# CH32V317W-R0-1v0.net
KiCad netlist of a schematic drawn in Altium Designer
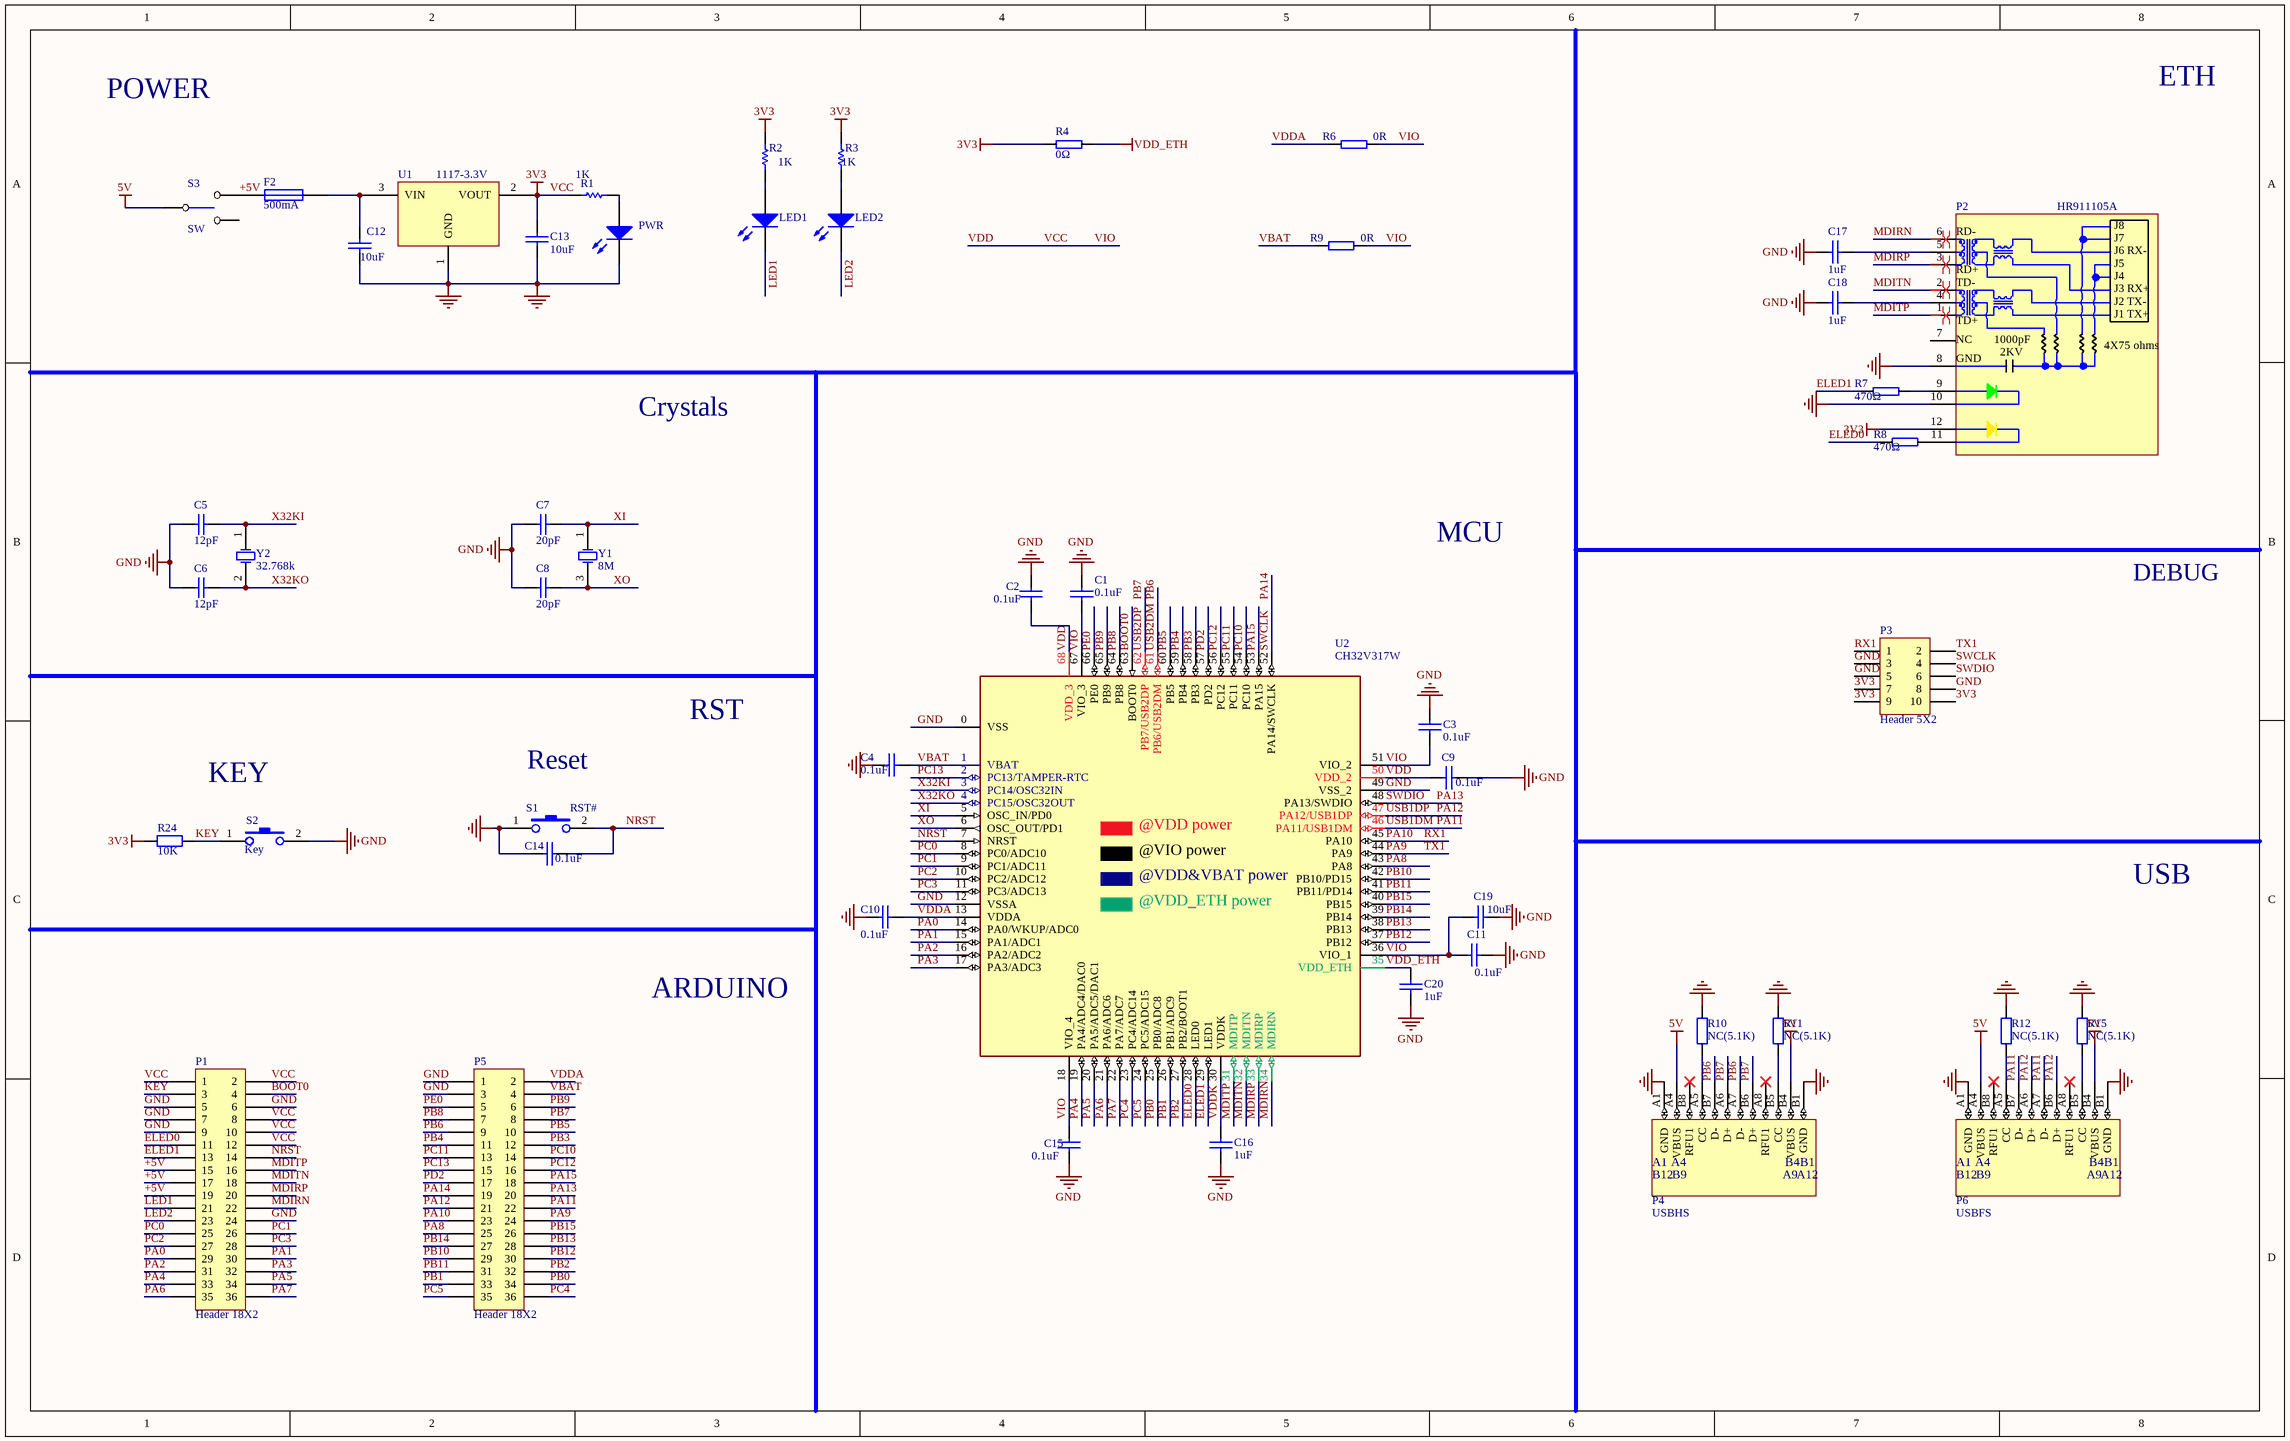
[diagram p0: CH32V317W-R0-1v0.SchDoc]

(export (version "E")
  (design (tool "Eeschema 10.0.6"))
  (components
    (comp (ref "C1")
      (value "0.1uF")
      (footprint "0603_C")
      (description "Capacitor")
      (libsource (lib "*") (part "CAP"))
    )
    (comp (ref "C2")
      (value "0.1uF")
      (footprint "0603_C")
      (description "Capacitor")
      (libsource (lib "*") (part "CAP"))
    )
    (comp (ref "C3")
      (value "0.1uF")
      (footprint "0603_C")
      (description "Capacitor")
      (libsource (lib "*") (part "CAP"))
    )
    (comp (ref "C4")
      (value "0.1uF")
      (footprint "0603_C")
      (description "Capacitor")
      (libsource (lib "*") (part "CAP"))
    )
    (comp (ref "C5")
      (value "12pF")
      (footprint "0603_C")
      (description "Capacitor")
      (libsource (lib "Miscellaneous Devices") (part "Cap"))
    )
    (comp (ref "C6")
      (value "12pF")
      (footprint "0603_C")
      (description "Capacitor")
      (libsource (lib "Miscellaneous Devices") (part "Cap"))
    )
    (comp (ref "C7")
      (value "20pF")
      (footprint "0603_C")
      (description "Capacitor")
      (libsource (lib "Miscellaneous Devices") (part "Cap"))
    )
    (comp (ref "C8")
      (value "20pF")
      (footprint "0603_C")
      (description "Capacitor")
      (libsource (lib "Miscellaneous Devices") (part "Cap"))
    )
    (comp (ref "C9")
      (value "0.1uF")
      (footprint "0603_C")
      (description "Capacitor")
      (libsource (lib "*") (part "CAP"))
    )
    (comp (ref "C10")
      (value "0.1uF")
      (footprint "0603_C")
      (description "Capacitor")
      (libsource (lib "*") (part "CAP"))
    )
    (comp (ref "C11")
      (value "0.1uF")
      (footprint "0603_C")
      (description "Capacitor")
      (libsource (lib "*") (part "CAP"))
    )
    (comp (ref "C12")
      (value "10uF")
      (footprint "0603_C")
      (description "Capacitor")
      (libsource (lib "*") (part "CAP"))
    )
    (comp (ref "C13")
      (value "10uF")
      (footprint "0603_C")
      (description "Capacitor")
      (libsource (lib "*") (part "CAP"))
    )
    (comp (ref "C14")
      (value "0.1uF")
      (footprint "0603_C")
      (description "Capacitor")
      (libsource (lib "") (part "CAP_1"))
    )
    (comp (ref "C15")
      (value "0.1uF")
      (footprint "0603_C")
      (description "Capacitor")
      (libsource (lib "*") (part "CAP"))
    )
    (comp (ref "C16")
      (value "1uF")
      (footprint "0603_C")
      (description "Capacitor")
      (libsource (lib "wch_sch_others") (part "CAP"))
    )
    (comp (ref "C17")
      (value "1uF")
      (footprint "0603_C")
      (description "Capacitor")
      (libsource (lib "wch_sch_others") (part "CAP"))
    )
    (comp (ref "C18")
      (value "1uF")
      (footprint "0603_C")
      (description "Capacitor")
      (libsource (lib "wch_sch_others") (part "CAP"))
    )
    (comp (ref "C19")
      (value "10uF")
      (footprint "0603_C")
      (description "Capacitor")
      (libsource (lib "*") (part "CAP"))
    )
    (comp (ref "C20")
      (value "1uF")
      (footprint "0603_C")
      (description "Capacitor")
      (libsource (lib "*") (part "CAP"))
    )
    (comp (ref "F2")
      (value "500mA")
      (footprint "0603")
      (description "Fuse")
      (libsource (lib "*") (part "FUSE1"))
    )
    (comp (ref "LED1")
      (value "LED1   blue")
      (footprint "0603+")
      (description "Typical INFRARED GaAs LED")
      (fields (field (name "PUBLISHER") "Altium Limited"))
      (libsource (lib "Miscellaneous Devices") (part "LED0"))
    )
    (comp (ref "LED2")
      (value "LED2  blue")
      (footprint "0603+")
      (description "Typical INFRARED GaAs LED")
      (fields (field (name "PUBLISHER") "Altium Limited"))
      (libsource (lib "Miscellaneous Devices") (part "LED0"))
    )
    (comp (ref "P1")
      (value "Header 18X2")
      (footprint "IDC36-2.54mm")
      (description "Header, 18-Pin, Dual row")
      (fields (field (name "PUBLISHER") "Altium Limited"))
      (libsource (lib "Miscellaneous Connectors") (part "Header 18X2"))
    )
    (comp (ref "P2") (value "HR911105A") (footprint "HR911105A") (libsource (lib "*") (part "HR911105A")))
    (comp (ref "P3")
      (value "Header 5X2")
      (footprint "IDC10-2.54mm")
      (description "Header, 5-Pin, Dual row")
      (fields (field (name "PUBLISHER") "Altium Limited"))
      (libsource (lib "Miscellaneous Connectors") (part "Header 5X2"))
    )
    (comp (ref "P4")
      (value "USBHS")
      (footprint "TYPE-C-Receptacle-2.0")
      (libsource (lib "*") (part "TYPE-C1"))
    )
    (comp (ref "P5")
      (value "Header 18X2")
      (footprint "IDC36-2.54mm")
      (description "Header, 18-Pin, Dual row")
      (fields (field (name "PUBLISHER") "Altium Limited"))
      (libsource (lib "Miscellaneous Connectors") (part "Header 18X2"))
    )
    (comp (ref "P6")
      (value "USBFS")
      (footprint "TYPE-C-Receptacle-2.0")
      (libsource (lib "*") (part "TYPE-C1"))
    )
    (comp (ref "PWR")
      (value "POWER  red")
      (footprint "0603+")
      (description "Typical INFRARED GaAs LED")
      (fields (field (name "PUBLISHER") "Altium Limited"))
      (libsource (lib "Miscellaneous Devices") (part "LED0"))
    )
    (comp (ref "R1")
      (value "1K")
      (footprint "0603")
      (description "Semiconductor Resistor")
      (libsource (lib "Miscellaneous Devices") (part "Res Semi"))
    )
    (comp (ref "R2")
      (value "1K")
      (footprint "0603")
      (description "Semiconductor Resistor")
      (libsource (lib "Miscellaneous Devices") (part "Res Semi"))
    )
    (comp (ref "R3")
      (value "1K")
      (footprint "0603")
      (description "Semiconductor Resistor")
      (libsource (lib "Miscellaneous Devices") (part "Res Semi"))
    )
    (comp (ref "R4") (value "0Ω") (footprint "0603") (libsource (lib "") (part "RES_1")))
    (comp (ref "R6") (value "0R") (footprint "0603") (libsource (lib "*") (part "R")))
    (comp (ref "R7") (value "470Ω") (footprint "0603") (libsource (lib "wch_sch_others") (part "RES")))
    (comp (ref "R8") (value "470Ω") (footprint "0603") (libsource (lib "wch_sch_others") (part "RES")))
    (comp (ref "R9") (value "0R") (footprint "0603") (libsource (lib "*") (part "R")))
    (comp (ref "R10")
      (value "NC(5.1K)")
      (footprint "0603")
      (description "Resistor")
      (libsource (lib "") (part "Res2_1"))
    )
    (comp (ref "R11")
      (value "NC(5.1K)")
      (footprint "0603")
      (description "Resistor")
      (libsource (lib "") (part "Res2_1"))
    )
    (comp (ref "R12")
      (value "NC(5.1K)")
      (footprint "0603")
      (description "Resistor")
      (libsource (lib "") (part "Res2_1"))
    )
    (comp (ref "R15")
      (value "NC(5.1K)")
      (footprint "0603")
      (description "Resistor")
      (libsource (lib "") (part "Res2_1"))
    )
    (comp (ref "R24")
      (value "10K")
      (footprint "0603")
      (description "Resistor")
      (libsource (lib "Miscellaneous Devices") (part "Res2"))
    )
    (comp (ref "S1")
      (value "RST#")
      (footprint "SMD_6.1x3.65x2.5mm-KEY")
      (libsource (lib "wch_sch_others") (part "KEY1"))
    )
    (comp (ref "S2")
      (value "Key")
      (footprint "SMD_6.1x3.65x2.5mm-KEY")
      (libsource (lib "wch_sch_others") (part "KEY1"))
    )
    (comp (ref "S3") (value "SW") (footprint "SW1") (libsource (lib "MYSCH") (part "SW")))
    (comp (ref "U1")
      (value "1117-3.3V")
      (footprint "SOT-223")
      (libsource (lib "wch_sch_others") (part "1117-3.3V"))
    )
    (comp (ref "U2")
      (value "CH32V317W")
      (footprint "QFN68_8X8")
      (description "RISC-V FPU HD-MCU, 144MHz, USB_480M, USB OTG, 100M Ethernet & Phy, 2*CAN")
      (libsource (lib "CHXXX") (part "CH32V317W"))
    )
    (comp (ref "Y1")
      (value "8M")
      (footprint "XT3225")
      (description "Crystal Oscillator")
      (fields (field (name "PUBLISHER") "Altium Limited"))
      (libsource (lib "") (part "XTAL_1"))
    )
    (comp (ref "Y2")
      (value "32.768k")
      (footprint "FC-135")
      (description "Crystal Oscillator")
      (fields (field (name "PUBLISHER") "Altium Limited"))
      (libsource (lib "Miscellaneous Devices") (part "XTAL"))
    )
  )
  (nets
    (net (code "1") (name "/+5V") (class "Default")
      (node (ref "F2") (pin "1") (pinfunction "1_1") (pintype "passive"))
      (node (ref "P1") (pin "15") (pinfunction "15_15") (pintype "passive"))
      (node (ref "P1") (pin "17") (pinfunction "17_17") (pintype "passive"))
      (node (ref "P1") (pin "19") (pinfunction "19_19") (pintype "passive"))
      (node (ref "S3") (pin "3") (pinfunction "3_3") (pintype "passive"))
    )
    (net (code "2") (name "/BOOT0") (class "Default")
      (node (ref "P1") (pin "4") (pinfunction "4_4") (pintype "passive"))
      (node (ref "U2") (pin "63") (pinfunction "BOOT0_63") (pintype "input"))
    )
    (net (code "3") (name "/ELED0") (class "Default")
      (node (ref "P1") (pin "11") (pinfunction "11_11") (pintype "passive"))
      (node (ref "R8") (pin "1") (pintype "passive"))
      (node (ref "U2") (pin "28") (pinfunction "LED0_28") (pintype "bidirectional"))
    )
    (net (code "4") (name "/ELED1") (class "Default")
      (node (ref "P1") (pin "13") (pinfunction "13_13") (pintype "passive"))
      (node (ref "R7") (pin "1") (pintype "passive"))
      (node (ref "U2") (pin "29") (pinfunction "LED1_29") (pintype "bidirectional"))
    )
    (net (code "5") (name "/KEY") (class "Default")
      (node (ref "P1") (pin "3") (pinfunction "3_3") (pintype "passive"))
      (node (ref "R24") (pin "1") (pinfunction "1_1") (pintype "passive"))
      (node (ref "S2") (pin "1") (pinfunction "1_1") (pintype "passive"))
    )
    (net (code "6") (name "/LED1") (class "Default")
      (node (ref "LED1") (pin "2") (pinfunction "K_2") (pintype "passive"))
      (node (ref "P1") (pin "21") (pinfunction "21_21") (pintype "passive"))
    )
    (net (code "7") (name "/LED2") (class "Default")
      (node (ref "LED2") (pin "2") (pinfunction "K_2") (pintype "passive"))
      (node (ref "P1") (pin "23") (pinfunction "23_23") (pintype "passive"))
    )
    (net (code "8") (name "/MDIRN") (class "Default")
      (node (ref "P1") (pin "22") (pinfunction "22_22") (pintype "passive"))
      (node (ref "P2") (pin "6") (pintype "passive"))
      (node (ref "U2") (pin "34") (pinfunction "MDIRN_34") (pintype "bidirectional"))
    )
    (net (code "9") (name "/MDIRP") (class "Default")
      (node (ref "P1") (pin "20") (pinfunction "20_20") (pintype "passive"))
      (node (ref "P2") (pin "3") (pintype "passive"))
      (node (ref "U2") (pin "33") (pinfunction "MDIRP_33") (pintype "bidirectional"))
    )
    (net (code "10") (name "/MDITN") (class "Default")
      (node (ref "P1") (pin "18") (pinfunction "18_18") (pintype "passive"))
      (node (ref "P2") (pin "2") (pintype "passive"))
      (node (ref "U2") (pin "32") (pinfunction "MDITN_32") (pintype "bidirectional"))
    )
    (net (code "11") (name "/MDITP") (class "Default")
      (node (ref "P1") (pin "16") (pinfunction "16_16") (pintype "passive"))
      (node (ref "P2") (pin "1") (pintype "passive"))
      (node (ref "U2") (pin "31") (pinfunction "MDITP_31") (pintype "bidirectional"))
    )
    (net (code "12") (name "/NRST") (class "Default")
      (node (ref "C14") (pin "2") (pinfunction "2_2") (pintype "passive"))
      (node (ref "P1") (pin "14") (pinfunction "14_14") (pintype "passive"))
      (node (ref "S1") (pin "2") (pinfunction "2_2") (pintype "passive"))
      (node (ref "U2") (pin "7") (pinfunction "NRST_7") (pintype "input"))
    )
    (net (code "13") (name "/PA0") (class "Default")
      (node (ref "P1") (pin "29") (pinfunction "29_29") (pintype "passive"))
      (node (ref "U2") (pin "14") (pinfunction "PA0/WKUP/ADC0_14") (pintype "bidirectional"))
    )
    (net (code "14") (name "/PA1") (class "Default")
      (node (ref "P1") (pin "30") (pinfunction "30_30") (pintype "passive"))
      (node (ref "U2") (pin "15") (pinfunction "PA1/ADC1_15") (pintype "bidirectional"))
    )
    (net (code "15") (name "/PA2") (class "Default")
      (node (ref "P1") (pin "31") (pinfunction "31_31") (pintype "passive"))
      (node (ref "U2") (pin "16") (pinfunction "PA2/ADC2_16") (pintype "bidirectional"))
    )
    (net (code "16") (name "/PA3") (class "Default")
      (node (ref "P1") (pin "32") (pinfunction "32_32") (pintype "passive"))
      (node (ref "U2") (pin "17") (pinfunction "PA3/ADC3_17") (pintype "bidirectional"))
    )
    (net (code "17") (name "/PA4") (class "Default")
      (node (ref "P1") (pin "33") (pinfunction "33_33") (pintype "passive"))
      (node (ref "U2") (pin "19") (pinfunction "PA4/ADC4/DAC0_19") (pintype "bidirectional"))
    )
    (net (code "18") (name "/PA5") (class "Default")
      (node (ref "P1") (pin "34") (pinfunction "34_34") (pintype "passive"))
      (node (ref "U2") (pin "20") (pinfunction "PA5/ADC5/DAC1_20") (pintype "bidirectional"))
    )
    (net (code "19") (name "/PA6") (class "Default")
      (node (ref "P1") (pin "35") (pinfunction "35_35") (pintype "passive"))
      (node (ref "U2") (pin "21") (pinfunction "PA6/ADC6_21") (pintype "bidirectional"))
    )
    (net (code "20") (name "/PA7") (class "Default")
      (node (ref "P1") (pin "36") (pinfunction "36_36") (pintype "passive"))
      (node (ref "U2") (pin "22") (pinfunction "PA7/ADC7_22") (pintype "bidirectional"))
    )
    (net (code "21") (name "/PA8") (class "Default")
      (node (ref "P5") (pin "25") (pinfunction "25_25") (pintype "passive"))
      (node (ref "U2") (pin "43") (pinfunction "PA8_43") (pintype "bidirectional"))
    )
    (net (code "22") (name "/PA9") (class "Default")
      (node (ref "P3") (pin "2") (pinfunction "2_2") (pintype "passive"))
      (node (ref "P5") (pin "24") (pinfunction "24_24") (pintype "passive"))
      (node (ref "U2") (pin "44") (pinfunction "PA9_44") (pintype "bidirectional"))
    )
    (net (code "23") (name "/PA10") (class "Default")
      (node (ref "P3") (pin "1") (pinfunction "1_1") (pintype "passive"))
      (node (ref "P5") (pin "23") (pinfunction "23_23") (pintype "passive"))
      (node (ref "U2") (pin "45") (pinfunction "PA10_45") (pintype "bidirectional"))
    )
    (net (code "24") (name "/PA11") (class "Default")
      (node (ref "P5") (pin "22") (pinfunction "22_22") (pintype "passive"))
      (node (ref "P6") (pin "A7") (pinfunction "D-_A7") (pintype "bidirectional"))
      (node (ref "P6") (pin "B7") (pinfunction "D-_B7") (pintype "bidirectional"))
      (node (ref "U2") (pin "46") (pinfunction "PA11/USB1DM_46") (pintype "bidirectional"))
    )
    (net (code "25") (name "/PA12") (class "Default")
      (node (ref "P5") (pin "21") (pinfunction "21_21") (pintype "passive"))
      (node (ref "P6") (pin "A6") (pinfunction "D+_A6") (pintype "bidirectional"))
      (node (ref "P6") (pin "B6") (pinfunction "D+_B6") (pintype "bidirectional"))
      (node (ref "U2") (pin "47") (pinfunction "PA12/USB1DP_47") (pintype "bidirectional"))
    )
    (net (code "26") (name "/PA13") (class "Default")
      (node (ref "P3") (pin "6") (pinfunction "6_6") (pintype "passive"))
      (node (ref "P5") (pin "20") (pinfunction "20_20") (pintype "passive"))
      (node (ref "U2") (pin "48") (pinfunction "PA13/SWDIO_48") (pintype "bidirectional"))
    )
    (net (code "27") (name "/PA14") (class "Default")
      (node (ref "P3") (pin "4") (pinfunction "4_4") (pintype "passive"))
      (node (ref "P5") (pin "19") (pinfunction "19_19") (pintype "passive"))
      (node (ref "U2") (pin "52") (pinfunction "PA14/SWCLK_52") (pintype "bidirectional"))
    )
    (net (code "28") (name "/PA15") (class "Default")
      (node (ref "P5") (pin "18") (pinfunction "18_18") (pintype "passive"))
      (node (ref "U2") (pin "53") (pinfunction "PA15_53") (pintype "bidirectional"))
    )
    (net (code "29") (name "/PB0") (class "Default")
      (node (ref "P5") (pin "34") (pinfunction "34_34") (pintype "passive"))
      (node (ref "U2") (pin "25") (pinfunction "PB0/ADC8_25") (pintype "bidirectional"))
    )
    (net (code "30") (name "/PB1") (class "Default")
      (node (ref "P5") (pin "33") (pinfunction "33_33") (pintype "passive"))
      (node (ref "U2") (pin "26") (pinfunction "PB1/ADC9_26") (pintype "bidirectional"))
    )
    (net (code "31") (name "/PB2") (class "Default")
      (node (ref "P5") (pin "32") (pinfunction "32_32") (pintype "passive"))
      (node (ref "U2") (pin "27") (pinfunction "PB2/BOOT1_27") (pintype "bidirectional"))
    )
    (net (code "32") (name "/PB3") (class "Default")
      (node (ref "P5") (pin "12") (pinfunction "12_12") (pintype "passive"))
      (node (ref "U2") (pin "58") (pinfunction "PB3_58") (pintype "bidirectional"))
    )
    (net (code "33") (name "/PB4") (class "Default")
      (node (ref "P5") (pin "11") (pinfunction "11_11") (pintype "passive"))
      (node (ref "U2") (pin "59") (pinfunction "PB4_59") (pintype "bidirectional"))
    )
    (net (code "34") (name "/PB5") (class "Default")
      (node (ref "P5") (pin "10") (pinfunction "10_10") (pintype "passive"))
      (node (ref "U2") (pin "60") (pinfunction "PB5_60") (pintype "bidirectional"))
    )
    (net (code "35") (name "/PB6") (class "Default")
      (node (ref "P4") (pin "A7") (pinfunction "D-_A7") (pintype "bidirectional"))
      (node (ref "P4") (pin "B7") (pinfunction "D-_B7") (pintype "bidirectional"))
      (node (ref "P5") (pin "9") (pinfunction "9_9") (pintype "passive"))
      (node (ref "U2") (pin "61") (pinfunction "PB6/USB2DM_61") (pintype "bidirectional"))
    )
    (net (code "36") (name "/PB7") (class "Default")
      (node (ref "P4") (pin "A6") (pinfunction "D+_A6") (pintype "bidirectional"))
      (node (ref "P4") (pin "B6") (pinfunction "D+_B6") (pintype "bidirectional"))
      (node (ref "P5") (pin "8") (pinfunction "8_8") (pintype "passive"))
      (node (ref "U2") (pin "62") (pinfunction "PB7/USB2DP_62") (pintype "bidirectional"))
    )
    (net (code "37") (name "/PB8") (class "Default")
      (node (ref "P5") (pin "7") (pinfunction "7_7") (pintype "passive"))
      (node (ref "U2") (pin "64") (pinfunction "PB8_64") (pintype "bidirectional"))
    )
    (net (code "38") (name "/PB9") (class "Default")
      (node (ref "P5") (pin "6") (pinfunction "6_6") (pintype "passive"))
      (node (ref "U2") (pin "65") (pinfunction "PB9_65") (pintype "bidirectional"))
    )
    (net (code "39") (name "/PB10") (class "Default")
      (node (ref "P5") (pin "29") (pinfunction "29_29") (pintype "passive"))
      (node (ref "U2") (pin "42") (pinfunction "PB10/PD15_42") (pintype "bidirectional"))
    )
    (net (code "40") (name "/PB11") (class "Default")
      (node (ref "P5") (pin "31") (pinfunction "31_31") (pintype "passive"))
      (node (ref "U2") (pin "41") (pinfunction "PB11/PD14_41") (pintype "bidirectional"))
    )
    (net (code "41") (name "/PB12") (class "Default")
      (node (ref "P5") (pin "30") (pinfunction "30_30") (pintype "passive"))
      (node (ref "U2") (pin "37") (pinfunction "PB12_37") (pintype "bidirectional"))
    )
    (net (code "42") (name "/PB13") (class "Default")
      (node (ref "P5") (pin "28") (pinfunction "28_28") (pintype "passive"))
      (node (ref "U2") (pin "38") (pinfunction "PB13_38") (pintype "bidirectional"))
    )
    (net (code "43") (name "/PB14") (class "Default")
      (node (ref "P5") (pin "27") (pinfunction "27_27") (pintype "passive"))
      (node (ref "U2") (pin "39") (pinfunction "PB14_39") (pintype "bidirectional"))
    )
    (net (code "44") (name "/PB15") (class "Default")
      (node (ref "P5") (pin "26") (pinfunction "26_26") (pintype "passive"))
      (node (ref "U2") (pin "40") (pinfunction "PB15_40") (pintype "bidirectional"))
    )
    (net (code "45") (name "/PC0") (class "Default")
      (node (ref "P1") (pin "25") (pinfunction "25_25") (pintype "passive"))
      (node (ref "U2") (pin "8") (pinfunction "PC0/ADC10_8") (pintype "bidirectional"))
    )
    (net (code "46") (name "/PC1") (class "Default")
      (node (ref "P1") (pin "26") (pinfunction "26_26") (pintype "passive"))
      (node (ref "U2") (pin "9") (pinfunction "PC1/ADC11_9") (pintype "bidirectional"))
    )
    (net (code "47") (name "/PC2") (class "Default")
      (node (ref "P1") (pin "27") (pinfunction "27_27") (pintype "passive"))
      (node (ref "U2") (pin "10") (pinfunction "PC2/ADC12_10") (pintype "bidirectional"))
    )
    (net (code "48") (name "/PC3") (class "Default")
      (node (ref "P1") (pin "28") (pinfunction "28_28") (pintype "passive"))
      (node (ref "U2") (pin "11") (pinfunction "PC3/ADC13_11") (pintype "bidirectional"))
    )
    (net (code "49") (name "/PC4") (class "Default")
      (node (ref "P5") (pin "36") (pinfunction "36_36") (pintype "passive"))
      (node (ref "U2") (pin "23") (pinfunction "PC4/ADC14_23") (pintype "bidirectional"))
    )
    (net (code "50") (name "/PC5") (class "Default")
      (node (ref "P5") (pin "35") (pinfunction "35_35") (pintype "passive"))
      (node (ref "U2") (pin "24") (pinfunction "PC5/ADC15_24") (pintype "bidirectional"))
    )
    (net (code "51") (name "/PC10") (class "Default")
      (node (ref "P5") (pin "14") (pinfunction "14_14") (pintype "passive"))
      (node (ref "U2") (pin "54") (pinfunction "PC10_54") (pintype "bidirectional"))
    )
    (net (code "52") (name "/PC11") (class "Default")
      (node (ref "P5") (pin "13") (pinfunction "13_13") (pintype "passive"))
      (node (ref "U2") (pin "55") (pinfunction "PC11_55") (pintype "bidirectional"))
    )
    (net (code "53") (name "/PC12") (class "Default")
      (node (ref "P5") (pin "16") (pinfunction "16_16") (pintype "passive"))
      (node (ref "U2") (pin "56") (pinfunction "PC12_56") (pintype "bidirectional"))
    )
    (net (code "54") (name "/PC13") (class "Default")
      (node (ref "P5") (pin "15") (pinfunction "15_15") (pintype "passive"))
      (node (ref "U2") (pin "2") (pinfunction "PC13/TAMPER-RTC_2") (pintype "bidirectional"))
    )
    (net (code "55") (name "/PD2") (class "Default")
      (node (ref "P5") (pin "17") (pinfunction "17_17") (pintype "passive"))
      (node (ref "U2") (pin "57") (pinfunction "PD2_57") (pintype "bidirectional"))
    )
    (net (code "56") (name "/PE0") (class "Default")
      (node (ref "P5") (pin "5") (pinfunction "5_5") (pintype "passive"))
      (node (ref "U2") (pin "66") (pinfunction "PE0_66") (pintype "bidirectional"))
    )
    (net (code "57") (name "/VBAT") (class "Default")
      (node (ref "C4") (pin "2") (pinfunction "2_2") (pintype "passive"))
      (node (ref "P5") (pin "4") (pinfunction "4_4") (pintype "passive"))
      (node (ref "R9") (pin "2") (pinfunction "2_2") (pintype "passive"))
      (node (ref "U2") (pin "1") (pinfunction "VBAT_1") (pintype "power_in"))
    )
    (net (code "58") (name "/VDDA") (class "Default")
      (node (ref "C10") (pin "1") (pinfunction "1_1") (pintype "passive"))
      (node (ref "P5") (pin "2") (pinfunction "2_2") (pintype "passive"))
      (node (ref "R6") (pin "2") (pinfunction "2_2") (pintype "passive"))
      (node (ref "U2") (pin "13") (pinfunction "VDDA_13") (pintype "power_in"))
    )
    (net (code "59") (name "/VDDK") (class "Default")
      (node (ref "C16") (pin "2") (pinfunction "2_2") (pintype "passive"))
      (node (ref "U2") (pin "30") (pinfunction "VDDK_30") (pintype "power_in"))
    )
    (net (code "60") (name "/X32KI") (class "Default")
      (node (ref "C5") (pin "1") (pinfunction "1_1") (pintype "passive"))
      (node (ref "U2") (pin "3") (pinfunction "PC14/OSC32IN_3") (pintype "bidirectional"))
      (node (ref "Y2") (pin "1") (pinfunction "OSC1_1") (pintype "passive"))
    )
    (net (code "61") (name "/X32KO") (class "Default")
      (node (ref "C6") (pin "1") (pinfunction "1_1") (pintype "passive"))
      (node (ref "U2") (pin "4") (pinfunction "PC15/OSC32OUT_4") (pintype "bidirectional"))
      (node (ref "Y2") (pin "2") (pinfunction "OSC2_2") (pintype "passive"))
    )
    (net (code "62") (name "/XI") (class "Default")
      (node (ref "C7") (pin "2") (pinfunction "2_2") (pintype "passive"))
      (node (ref "U2") (pin "5") (pinfunction "OSC_IN/PD0_5") (pintype "input"))
      (node (ref "Y1") (pin "1") (pinfunction "OSC1_1") (pintype "passive"))
    )
    (net (code "63") (name "/XO") (class "Default")
      (node (ref "C8") (pin "2") (pinfunction "2_2") (pintype "passive"))
      (node (ref "U2") (pin "6") (pinfunction "OSC_OUT/PD1_6") (pintype "output"))
      (node (ref "Y1") (pin "3") (pinfunction "OSC2_3") (pintype "passive"))
    )
    (net (code "64") (name "3V3") (class "Default")
      (node (ref "C1") (pin "2") (pinfunction "2_2") (pintype "passive"))
      (node (ref "C11") (pin "2") (pinfunction "2_2") (pintype "passive"))
      (node (ref "C13") (pin "1") (pinfunction "1_1") (pintype "passive"))
      (node (ref "C15") (pin "2") (pinfunction "2_2") (pintype "passive"))
      (node (ref "C19") (pin "2") (pinfunction "2_2") (pintype "passive"))
      (node (ref "C2") (pin "2") (pinfunction "2_2") (pintype "passive"))
      (node (ref "C3") (pin "2") (pinfunction "2_2") (pintype "passive"))
      (node (ref "C9") (pin "2") (pinfunction "2_2") (pintype "passive"))
      (node (ref "P1") (pin "1") (pinfunction "1_1") (pintype "passive"))
      (node (ref "P1") (pin "10") (pinfunction "10_10") (pintype "passive"))
      (node (ref "P1") (pin "12") (pinfunction "12_12") (pintype "passive"))
      (node (ref "P1") (pin "2") (pinfunction "2_2") (pintype "passive"))
      (node (ref "P1") (pin "8") (pinfunction "8_8") (pintype "passive"))
      (node (ref "P2") (pin "12") (pintype "passive"))
      (node (ref "P3") (pin "10") (pinfunction "10_10") (pintype "passive"))
      (node (ref "P3") (pin "7") (pinfunction "7_7") (pintype "passive"))
      (node (ref "P3") (pin "9") (pinfunction "9_9") (pintype "passive"))
      (node (ref "R1") (pin "2") (pinfunction "2_2") (pintype "passive"))
      (node (ref "R2") (pin "1") (pinfunction "1_1") (pintype "passive"))
      (node (ref "R24") (pin "2") (pinfunction "2_2") (pintype "passive"))
      (node (ref "R3") (pin "1") (pinfunction "1_1") (pintype "passive"))
      (node (ref "R4") (pin "2") (pintype "passive"))
      (node (ref "R6") (pin "1") (pinfunction "1_1") (pintype "passive"))
      (node (ref "R9") (pin "1") (pinfunction "1_1") (pintype "passive"))
      (node (ref "U1") (pin "2") (pinfunction "VOUT_2") (pintype "passive"))
      (node (ref "U2") (pin "18") (pinfunction "VIO_4_18") (pintype "power_in"))
      (node (ref "U2") (pin "36") (pinfunction "VIO_1_36") (pintype "power_in"))
      (node (ref "U2") (pin "50") (pinfunction "VDD_2_50") (pintype "power_in"))
      (node (ref "U2") (pin "51") (pinfunction "VIO_2_51") (pintype "power_in"))
      (node (ref "U2") (pin "67") (pinfunction "VIO_3_67") (pintype "power_in"))
      (node (ref "U2") (pin "68") (pinfunction "VDD_3_68") (pintype "power_in"))
    )
    (net (code "65") (name "5V") (class "Default")
      (node (ref "P4") (pin "A4") (pinfunction "VBUS_A4") (pintype "bidirectional"))
      (node (ref "P4") (pin "B4") (pinfunction "VBUS_B4") (pintype "bidirectional"))
      (node (ref "P6") (pin "A4") (pinfunction "VBUS_A4") (pintype "bidirectional"))
      (node (ref "P6") (pin "B4") (pinfunction "VBUS_B4") (pintype "bidirectional"))
      (node (ref "S3") (pin "1") (pinfunction "1_1") (pintype "passive"))
    )
    (net (code "66") (name "GND") (class "Default")
      (node (ref "C1") (pin "1") (pinfunction "1_1") (pintype "passive"))
      (node (ref "C10") (pin "2") (pinfunction "2_2") (pintype "passive"))
      (node (ref "C11") (pin "1") (pinfunction "1_1") (pintype "passive"))
      (node (ref "C12") (pin "2") (pinfunction "2_2") (pintype "passive"))
      (node (ref "C13") (pin "2") (pinfunction "2_2") (pintype "passive"))
      (node (ref "C14") (pin "1") (pinfunction "1_1") (pintype "passive"))
      (node (ref "C15") (pin "1") (pinfunction "1_1") (pintype "passive"))
      (node (ref "C16") (pin "1") (pinfunction "1_1") (pintype "passive"))
      (node (ref "C17") (pin "1") (pinfunction "1_1") (pintype "passive"))
      (node (ref "C18") (pin "1") (pinfunction "1_1") (pintype "passive"))
      (node (ref "C19") (pin "1") (pinfunction "1_1") (pintype "passive"))
      (node (ref "C2") (pin "1") (pinfunction "1_1") (pintype "passive"))
      (node (ref "C20") (pin "1") (pinfunction "1_1") (pintype "passive"))
      (node (ref "C3") (pin "1") (pinfunction "1_1") (pintype "passive"))
      (node (ref "C4") (pin "1") (pinfunction "1_1") (pintype "passive"))
      (node (ref "C5") (pin "2") (pinfunction "2_2") (pintype "passive"))
      (node (ref "C6") (pin "2") (pinfunction "2_2") (pintype "passive"))
      (node (ref "C7") (pin "1") (pinfunction "1_1") (pintype "passive"))
      (node (ref "C8") (pin "1") (pinfunction "1_1") (pintype "passive"))
      (node (ref "C9") (pin "1") (pinfunction "1_1") (pintype "passive"))
      (node (ref "P1") (pin "24") (pinfunction "24_24") (pintype "passive"))
      (node (ref "P1") (pin "5") (pinfunction "5_5") (pintype "passive"))
      (node (ref "P1") (pin "6") (pinfunction "6_6") (pintype "passive"))
      (node (ref "P1") (pin "7") (pinfunction "7_7") (pintype "passive"))
      (node (ref "P1") (pin "9") (pinfunction "9_9") (pintype "passive"))
      (node (ref "P2") (pin "10") (pintype "passive"))
      (node (ref "P2") (pin "8") (pintype "passive"))
      (node (ref "P3") (pin "3") (pinfunction "3_3") (pintype "passive"))
      (node (ref "P3") (pin "5") (pinfunction "5_5") (pintype "passive"))
      (node (ref "P3") (pin "8") (pinfunction "8_8") (pintype "passive"))
      (node (ref "P4") (pin "A1") (pinfunction "GND_A1") (pintype "bidirectional"))
      (node (ref "P4") (pin "B1") (pinfunction "GND_B1") (pintype "bidirectional"))
      (node (ref "P5") (pin "1") (pinfunction "1_1") (pintype "passive"))
      (node (ref "P5") (pin "3") (pinfunction "3_3") (pintype "passive"))
      (node (ref "P6") (pin "A1") (pinfunction "GND_A1") (pintype "bidirectional"))
      (node (ref "P6") (pin "B1") (pinfunction "GND_B1") (pintype "bidirectional"))
      (node (ref "PWR") (pin "2") (pinfunction "K_2") (pintype "passive"))
      (node (ref "R10") (pin "1") (pinfunction "1_1") (pintype "passive"))
      (node (ref "R11") (pin "1") (pinfunction "1_1") (pintype "passive"))
      (node (ref "R12") (pin "1") (pinfunction "1_1") (pintype "passive"))
      (node (ref "R15") (pin "1") (pinfunction "1_1") (pintype "passive"))
      (node (ref "S1") (pin "1") (pinfunction "1_1") (pintype "passive"))
      (node (ref "S2") (pin "2") (pinfunction "2_2") (pintype "passive"))
      (node (ref "U1") (pin "1") (pinfunction "GND_1") (pintype "passive"))
      (node (ref "U2") (pin "0") (pinfunction "VSS_0") (pintype "power_in"))
      (node (ref "U2") (pin "12") (pinfunction "VSSA_12") (pintype "power_in"))
      (node (ref "U2") (pin "49") (pinfunction "VSS_2_49") (pintype "power_in"))
    )
    (net (code "67") (name "Net-(C17-Pad2)") (class "Default")
      (node (ref "C17") (pin "2") (pinfunction "2_2") (pintype "passive"))
      (node (ref "P2") (pin "5") (pintype "passive"))
    )
    (net (code "68") (name "Net-(C18-Pad2)") (class "Default")
      (node (ref "C18") (pin "2") (pinfunction "2_2") (pintype "passive"))
      (node (ref "P2") (pin "4") (pintype "passive"))
    )
    (net (code "69") (name "Net-(LED1-A)") (class "Default")
      (node (ref "LED1") (pin "1") (pinfunction "A_1") (pintype "passive"))
      (node (ref "R2") (pin "2") (pinfunction "2_2") (pintype "passive"))
    )
    (net (code "70") (name "Net-(LED2-A)") (class "Default")
      (node (ref "LED2") (pin "1") (pinfunction "A_1") (pintype "passive"))
      (node (ref "R3") (pin "2") (pinfunction "2_2") (pintype "passive"))
    )
    (net (code "71") (name "Net-(P2-Pad9)") (class "Default")
      (node (ref "P2") (pin "9") (pintype "passive"))
      (node (ref "R7") (pin "2") (pintype "passive"))
    )
    (net (code "72") (name "Net-(P2-Pad11)") (class "Default")
      (node (ref "P2") (pin "11") (pintype "passive"))
      (node (ref "R8") (pin "2") (pintype "passive"))
    )
    (net (code "73") (name "Net-(P4-CC-PadA5)") (class "Default")
      (node (ref "P4") (pin "A5") (pinfunction "CC_A5") (pintype "bidirectional"))
      (node (ref "R10") (pin "2") (pinfunction "2_2") (pintype "passive"))
    )
    (net (code "74") (name "Net-(P4-CC-PadB5)") (class "Default")
      (node (ref "P4") (pin "B5") (pinfunction "CC_B5") (pintype "bidirectional"))
      (node (ref "R11") (pin "2") (pinfunction "2_2") (pintype "passive"))
    )
    (net (code "75") (name "Net-(P6-CC-PadA5)") (class "Default")
      (node (ref "P6") (pin "A5") (pinfunction "CC_A5") (pintype "bidirectional"))
      (node (ref "R12") (pin "2") (pinfunction "2_2") (pintype "passive"))
    )
    (net (code "76") (name "Net-(P6-CC-PadB5)") (class "Default")
      (node (ref "P6") (pin "B5") (pinfunction "CC_B5") (pintype "bidirectional"))
      (node (ref "R15") (pin "2") (pinfunction "2_2") (pintype "passive"))
    )
    (net (code "77") (name "Net-(PWR-A)") (class "Default")
      (node (ref "PWR") (pin "1") (pinfunction "A_1") (pintype "passive"))
      (node (ref "R1") (pin "1") (pinfunction "1_1") (pintype "passive"))
    )
    (net (code "78") (name "Net-(U1-VIN)") (class "Default")
      (node (ref "C12") (pin "1") (pinfunction "1_1") (pintype "passive"))
      (node (ref "F2") (pin "2") (pinfunction "2_2") (pintype "passive"))
      (node (ref "U1") (pin "3") (pinfunction "VIN_3") (pintype "passive"))
    )
    (net (code "79") (name "VDD_ETH") (class "Default")
      (node (ref "C20") (pin "2") (pinfunction "2_2") (pintype "passive"))
      (node (ref "R4") (pin "1") (pintype "passive"))
      (node (ref "U2") (pin "35") (pinfunction "VDD_ETH_35") (pintype "power_in"))
    )
    (net (code "80") (name "unconnected-(P2-Pad7)") (class "Default")
      (node (ref "P2") (pin "7") (pintype "passive"))
    )
    (net (code "81") (name "unconnected-(P4-RFU1-PadA8)") (class "Default")
      (node (ref "P4") (pin "A8") (pinfunction "RFU1_A8") (pintype "bidirectional+no_connect"))
    )
    (net (code "82") (name "unconnected-(P4-RFU1-PadB8)") (class "Default")
      (node (ref "P4") (pin "B8") (pinfunction "RFU1_B8") (pintype "bidirectional+no_connect"))
    )
    (net (code "83") (name "unconnected-(P6-RFU1-PadA8)") (class "Default")
      (node (ref "P6") (pin "A8") (pinfunction "RFU1_A8") (pintype "bidirectional+no_connect"))
    )
    (net (code "84") (name "unconnected-(P6-RFU1-PadB8)") (class "Default")
      (node (ref "P6") (pin "B8") (pinfunction "RFU1_B8") (pintype "bidirectional+no_connect"))
    )
    (net (code "85") (name "unconnected-(S3-Pad2)") (class "Default")
      (node (ref "S3") (pin "2") (pinfunction "2_2") (pintype "passive"))
    )
  )
)
